# MAZ000167_-_Diagrama_el_ctrico.net
KiCad netlist of a schematic drawn in Altium Designer
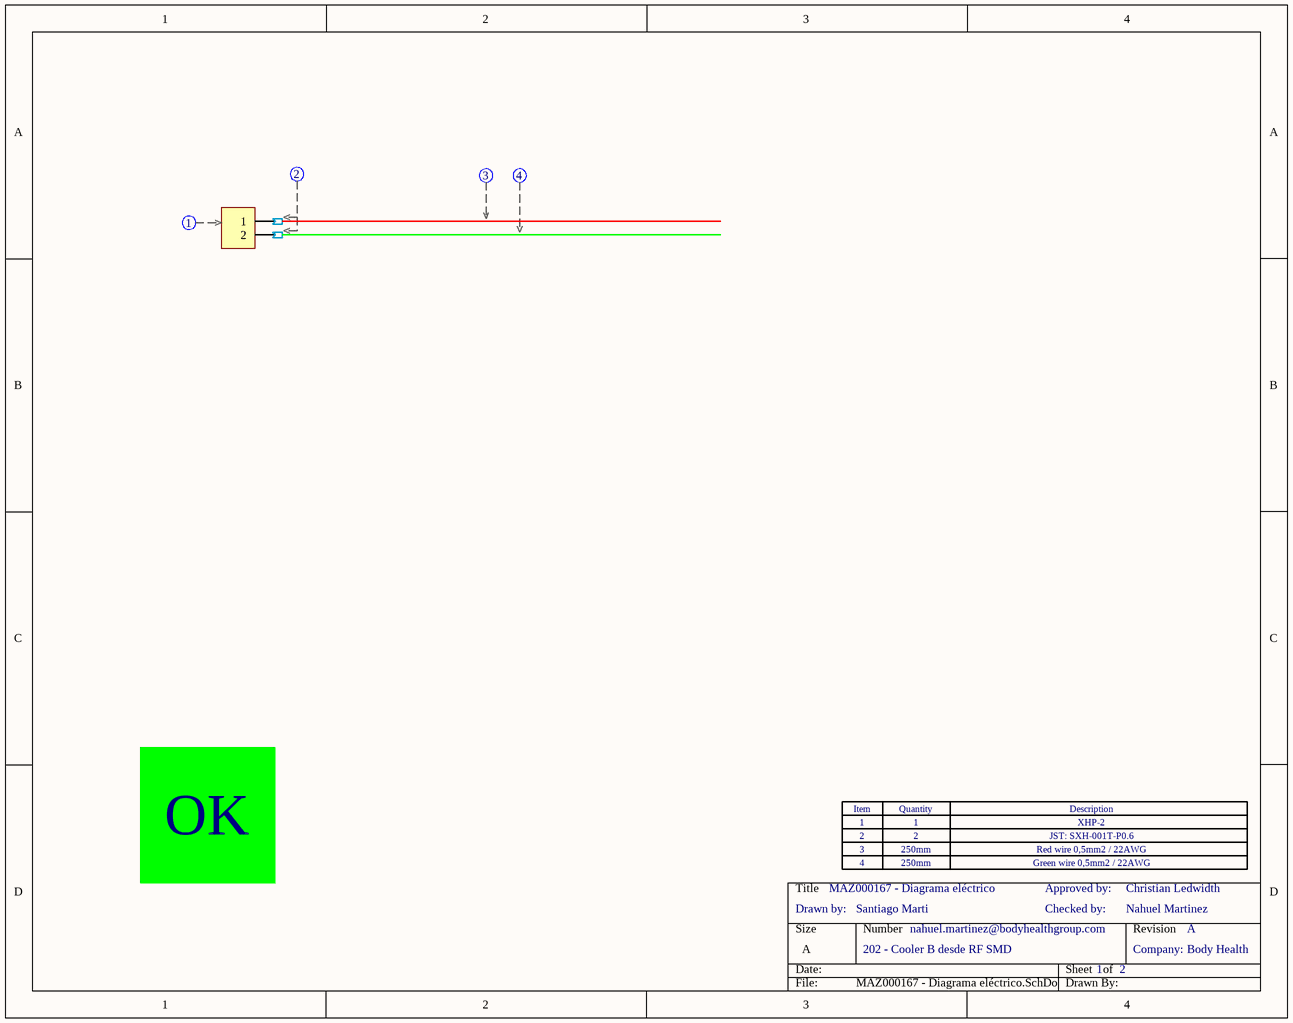
[diagram p0: MAZ000167 - Diagrama eléctrico.SchDoc]

(export (version "E")
  (design (tool "Eeschema 10.0.6"))
  (components
    (comp (ref "Con1")
      (value "XHP-2")
      (description "CONN HOUSING 2.5MM 2POS")
      (libsource (lib "LibreriaParaPlanos") (part "XHP-2"))
    )
    (comp (ref "Soc1")
      (value "sock_XHP_SXH-002T-P0.6")
      (description "CONN SOCKET 26-30AWG CRIMP TIN")
      (libsource (lib "LibreriaParaPlanos") (part "sock_XHP_SXH-002T-P0.6"))
    )
    (comp (ref "Soc2")
      (value "sock_XHP_SXH-002T-P0.6")
      (description "CONN SOCKET 26-30AWG CRIMP TIN")
      (libsource (lib "LibreriaParaPlanos") (part "sock_XHP_SXH-002T-P0.6"))
    )
    (comp (ref "Soc4")
      (value "sock_XHP_SXH-002T-P0.6")
      (description "CONN SOCKET 26-30AWG CRIMP TIN")
      (libsource (lib "LibreriaParaPlanos") (part "sock_XHP_SXH-002T-P0.6"))
    )
    (comp (ref "Zoc1")
      (value "Zócalo_Header")
      (description "Header para el zócalo de referencias")
      (libsource (lib "LibreriaParaPlanos") (part "Zócalo_Header"))
    )
    (comp (ref "Zoc2")
      (value "Zócalo_Item")
      (description "Ítem para el zócalo de referencias")
      (libsource (lib "LibreriaParaPlanos") (part "Zócalo_Item"))
    )
    (comp (ref "Zoc3")
      (value "Zócalo_Item")
      (description "Ítem para el zócalo de referencias")
      (libsource (lib "LibreriaParaPlanos") (part "Zócalo_Item"))
    )
    (comp (ref "Zoc4")
      (value "Zócalo_Item")
      (description "Ítem para el zócalo de referencias")
      (libsource (lib "LibreriaParaPlanos") (part "Zócalo_Item"))
    )
    (comp (ref "Zoc5")
      (value "Zócalo_Item")
      (description "Ítem para el zócalo de referencias")
      (libsource (lib "LibreriaParaPlanos") (part "Zócalo_Item"))
    )
  )
  (nets
    (net (code "1") (name "Net-(Con1-Pad1)") (class "Default")
      (node (ref "Con1") (pin "1") (pinfunction "1_1") (pintype "passive"))
      (node (ref "Soc1") (pin "0") (pinfunction "0_0") (pintype "passive"))
    )
    (net (code "2") (name "Net-(Con1-Pad2)") (class "Default")
      (node (ref "Con1") (pin "2") (pinfunction "2_2") (pintype "passive"))
      (node (ref "Soc2") (pin "0") (pinfunction "0_0") (pintype "passive"))
    )
    (net (code "3") (name "unconnected-(Soc1-Pad1)") (class "Default")
      (node (ref "Soc1") (pin "1") (pinfunction "1_1") (pintype "passive"))
    )
    (net (code "4") (name "unconnected-(Soc2-Pad1)") (class "Default")
      (node (ref "Soc2") (pin "1") (pinfunction "1_1") (pintype "passive"))
    )
  )
)
